# SCH_FINAL.net
KiCad netlist of a schematic drawn in EasyEDA
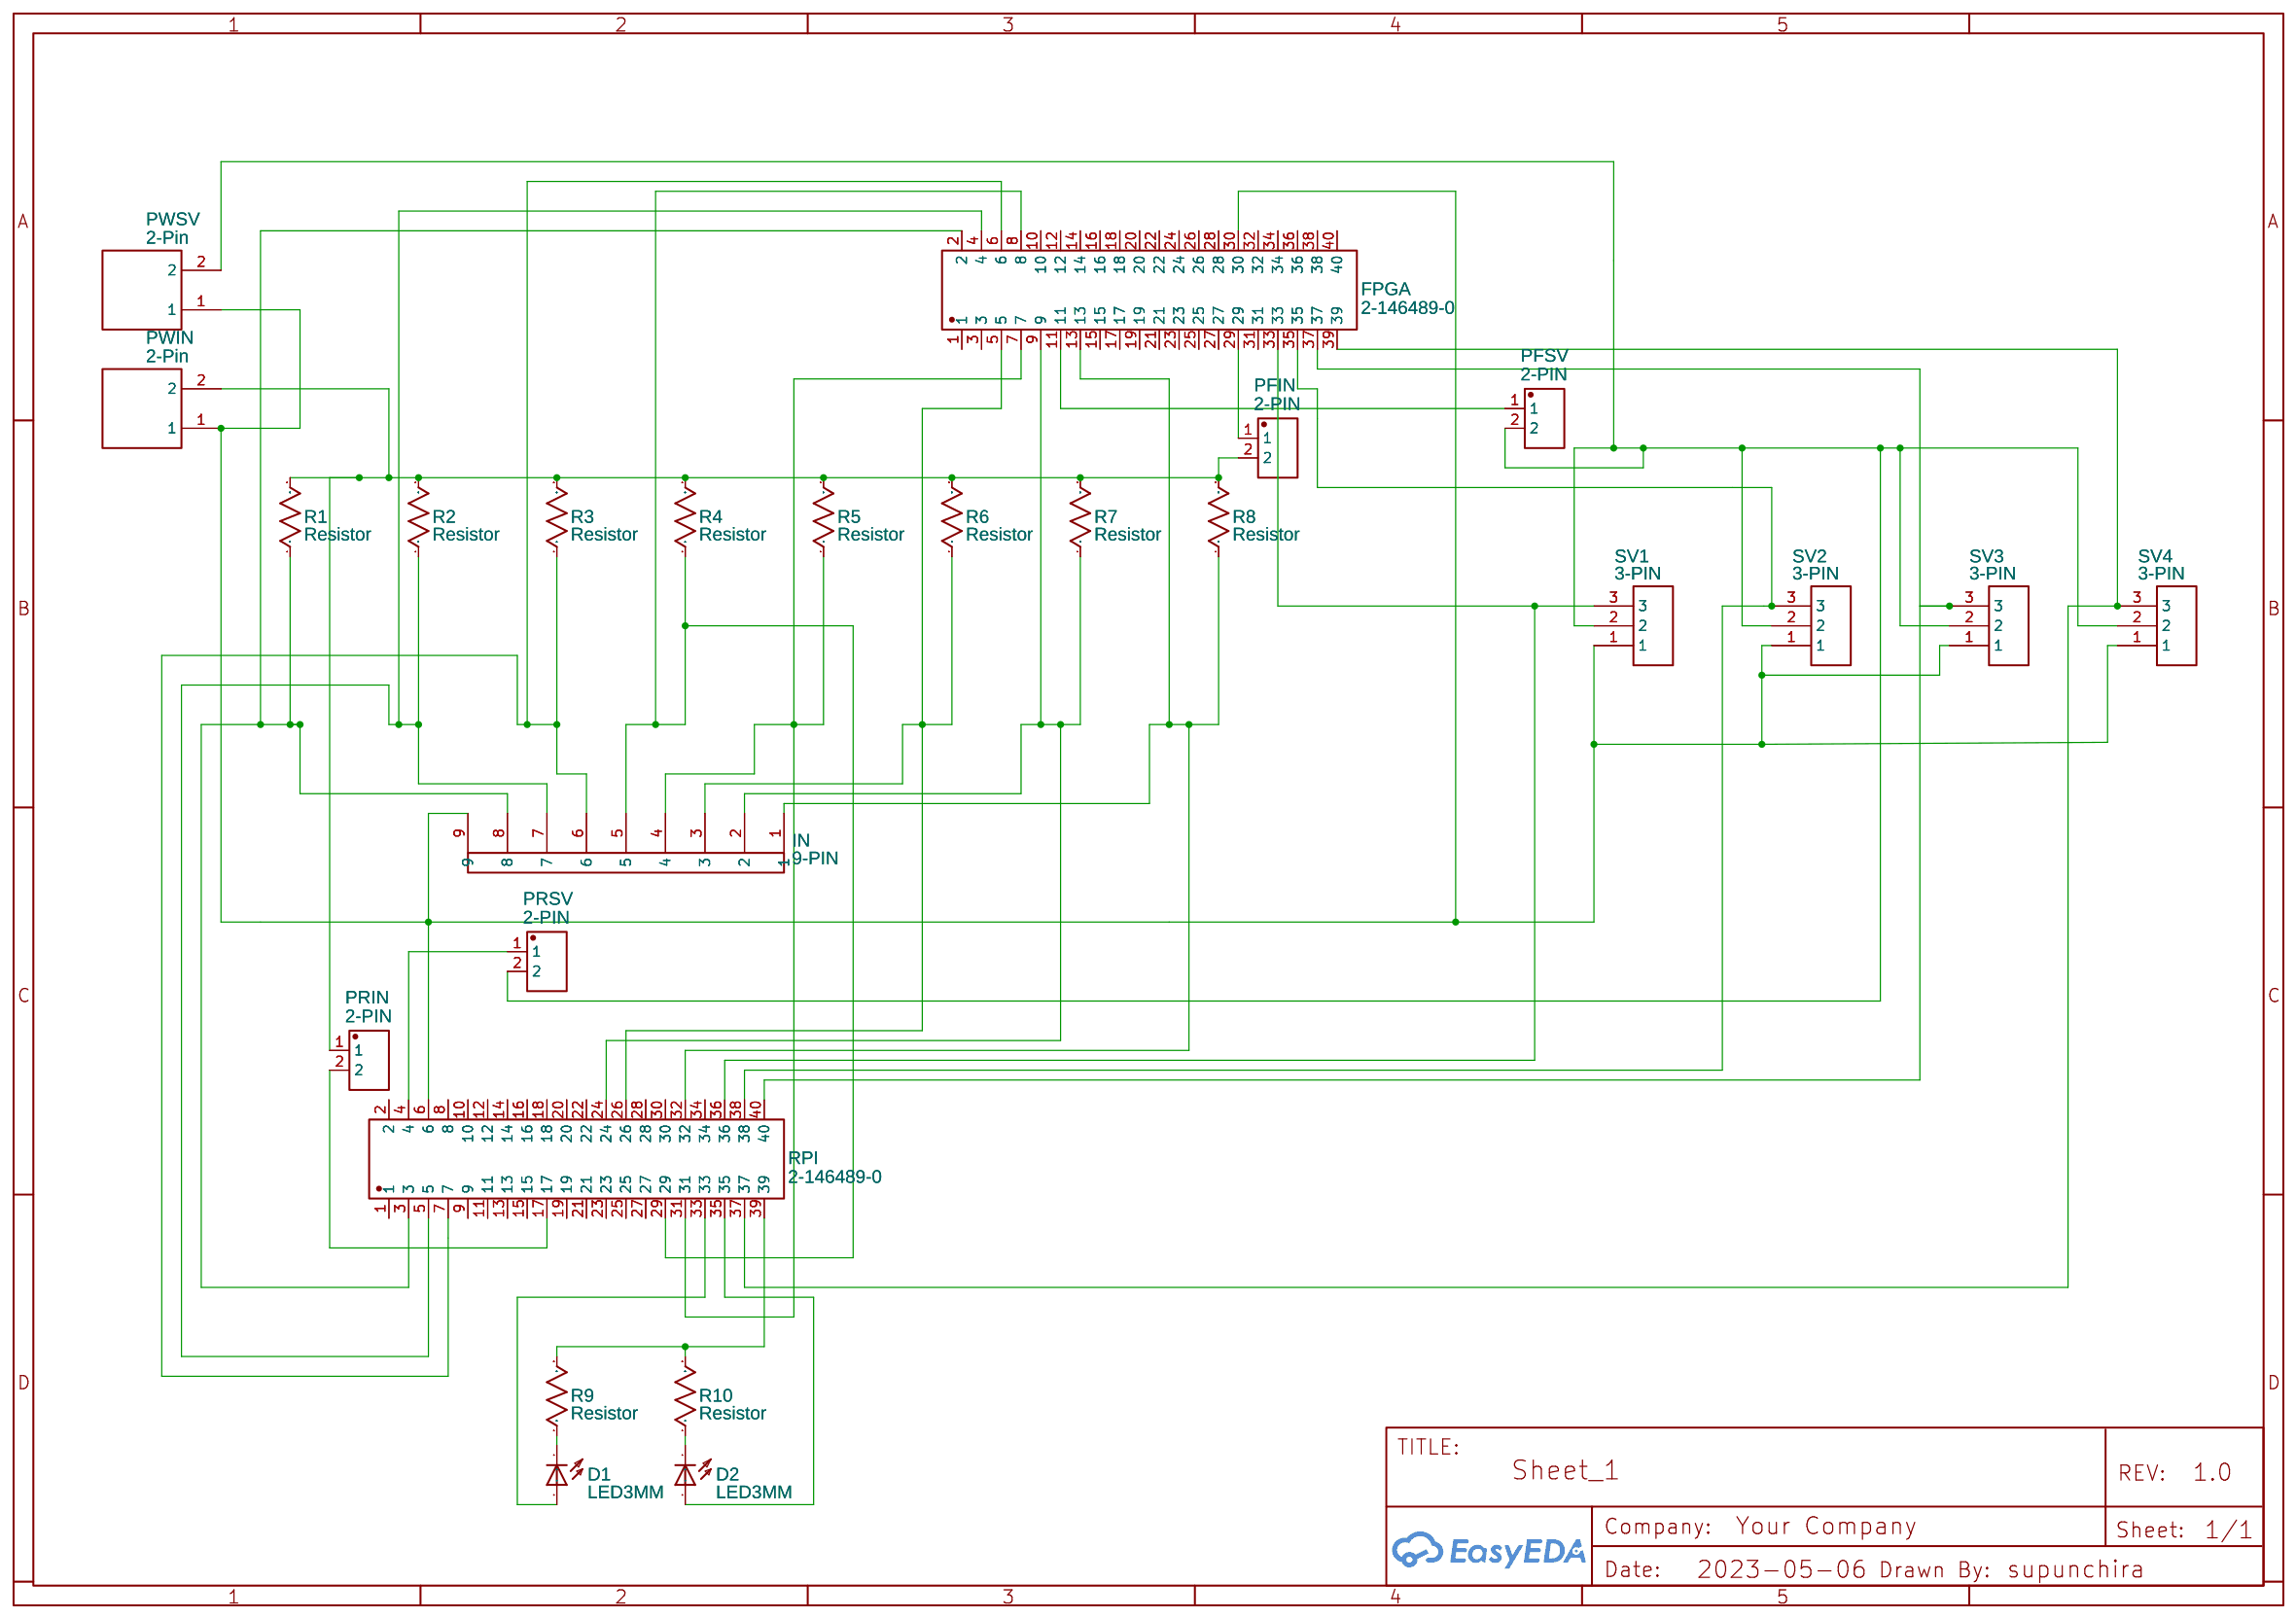
[diagram p0: schematic sheet]

(export (version "E")
  (design (tool "Eeschema 10.0.6"))
  (components
    (comp (ref "D1") (value "LED3MM") (libsource (lib "") (part "LED3MM")))
    (comp (ref "D2") (value "LED3MM") (libsource (lib "") (part "LED3MM")))
    (comp (ref "FPGA")
      (value "2-146489-0")
      (fields (field (name "BOM_Supplier Part") "C3334839"))
      (libsource (lib "") (part "2-146489-0_1"))
    )
    (comp (ref "IN") (value "9-PIN") (libsource (lib "") (part "Header9Pin")))
    (comp (ref "PFIN")
      (value "2-PIN")
      (fields
        (field (name "BOM_Manufacturer Part") "Terminals/WJ2EDGV-5.08-8P")
        (field (name "BOM_Supplier Part") "C23595")
      )
      (libsource (lib "") (part "2-PIN-MALE-CONNECTOR COPY_2"))
    )
    (comp (ref "PFSV")
      (value "2-PIN")
      (fields
        (field (name "BOM_Manufacturer Part") "Terminals/WJ2EDGV-5.08-8P")
        (field (name "BOM_Supplier Part") "C23595")
      )
      (libsource (lib "") (part "2-PIN-MALE-CONNECTOR COPY_1"))
    )
    (comp (ref "PRIN")
      (value "2-PIN")
      (fields
        (field (name "BOM_Manufacturer Part") "Terminals/WJ2EDGV-5.08-8P")
        (field (name "BOM_Supplier Part") "C23595")
      )
      (libsource (lib "") (part "2-PIN-MALE-CONNECTOR COPY"))
    )
    (comp (ref "PRSV")
      (value "2-PIN")
      (fields
        (field (name "BOM_Manufacturer Part") "Terminals/WJ2EDGV-5.08-8P")
        (field (name "BOM_Supplier Part") "C23595")
      )
      (libsource (lib "") (part "2-PIN-MALE-CONNECTOR COPY_3"))
    )
    (comp (ref "PWIN") (value "2-Pin") (libsource (lib "") (part "2-Pin-Male-Header-2.54mm_1")))
    (comp (ref "PWSV") (value "2-Pin") (libsource (lib "") (part "2-Pin-Male-Header-2.54mm")))
    (comp (ref "R1") (value "Resistor") (libsource (lib "") (part "Resistor")))
    (comp (ref "R2") (value "Resistor") (libsource (lib "") (part "Resistor")))
    (comp (ref "R3") (value "Resistor") (libsource (lib "") (part "Resistor")))
    (comp (ref "R4") (value "Resistor") (libsource (lib "") (part "Resistor")))
    (comp (ref "R5") (value "Resistor") (libsource (lib "") (part "Resistor")))
    (comp (ref "R6") (value "Resistor") (libsource (lib "") (part "Resistor")))
    (comp (ref "R7") (value "Resistor") (libsource (lib "") (part "Resistor")))
    (comp (ref "R8") (value "Resistor") (libsource (lib "") (part "Resistor")))
    (comp (ref "R9") (value "Resistor") (libsource (lib "") (part "Resistor")))
    (comp (ref "R10") (value "Resistor") (libsource (lib "") (part "Resistor")))
    (comp (ref "RPI")
      (value "2-146489-0")
      (fields (field (name "BOM_Supplier Part") "C3334839"))
      (libsource (lib "") (part "2-146489-0"))
    )
    (comp (ref "SV1") (value "3-PIN") (libsource (lib "") (part "3-PIN")))
    (comp (ref "SV2") (value "3-PIN") (libsource (lib "") (part "3-PIN")))
    (comp (ref "SV3") (value "3-PIN") (libsource (lib "") (part "3-PIN")))
    (comp (ref "SV4") (value "3-PIN") (libsource (lib "") (part "3-PIN")))
  )
  (nets
    (net (code "1") (name "Net-(D1-C)") (class "Default")
      (node (ref "D1") (pin "K") (pinfunction "C_K") (pintype "bidirectional"))
      (node (ref "R9") (pin "1") (pinfunction "P1_1") (pintype "unspecified"))
    )
    (net (code "2") (name "Net-(D1-PadA)") (class "Default")
      (node (ref "D1") (pin "A") (pinfunction "A_A") (pintype "bidirectional"))
      (node (ref "RPI") (pin "33") (pinfunction "33_33") (pintype "unspecified"))
    )
    (net (code "3") (name "Net-(D2-C)") (class "Default")
      (node (ref "D2") (pin "K") (pinfunction "C_K") (pintype "bidirectional"))
      (node (ref "R10") (pin "1") (pinfunction "P1_1") (pintype "unspecified"))
    )
    (net (code "4") (name "Net-(D2-PadA)") (class "Default")
      (node (ref "D2") (pin "A") (pinfunction "A_A") (pintype "bidirectional"))
      (node (ref "RPI") (pin "35") (pinfunction "35_35") (pintype "unspecified"))
    )
    (net (code "5") (name "Net-(FPGA-Pad11)") (class "Default")
      (node (ref "FPGA") (pin "11") (pinfunction "11_11") (pintype "unspecified"))
      (node (ref "PFSV") (pin "1") (pinfunction "1_1") (pintype "unspecified"))
    )
    (net (code "6") (name "Net-(FPGA-Pad29)") (class "Default")
      (node (ref "FPGA") (pin "29") (pinfunction "29_29") (pintype "unspecified"))
      (node (ref "PFIN") (pin "1") (pinfunction "1_1") (pintype "unspecified"))
    )
    (net (code "7") (name "Net-(FPGA-Pad30)") (class "Default")
      (node (ref "FPGA") (pin "30") (pinfunction "30_30") (pintype "unspecified"))
      (node (ref "IN") (pin "9") (pinfunction "9_9") (pintype "unspecified"))
      (node (ref "PWIN") (pin "1") (pinfunction "1_1") (pintype "unspecified"))
      (node (ref "PWSV") (pin "1") (pinfunction "1_1") (pintype "unspecified"))
      (node (ref "RPI") (pin "6") (pinfunction "6_6") (pintype "unspecified"))
      (node (ref "SV1") (pin "1") (pinfunction "1_1") (pintype "unspecified"))
      (node (ref "SV2") (pin "1") (pinfunction "1_1") (pintype "unspecified"))
      (node (ref "SV3") (pin "1") (pinfunction "1_1") (pintype "unspecified"))
      (node (ref "SV4") (pin "1") (pinfunction "1_1") (pintype "unspecified"))
    )
    (net (code "8") (name "Net-(FPGA-Pad33)") (class "Default")
      (node (ref "FPGA") (pin "33") (pinfunction "33_33") (pintype "unspecified"))
      (node (ref "RPI") (pin "36") (pinfunction "36_36") (pintype "unspecified"))
      (node (ref "SV1") (pin "3") (pinfunction "3_3") (pintype "unspecified"))
    )
    (net (code "9") (name "Net-(FPGA-Pad35)") (class "Default")
      (node (ref "FPGA") (pin "35") (pinfunction "35_35") (pintype "unspecified"))
      (node (ref "RPI") (pin "38") (pinfunction "38_38") (pintype "unspecified"))
      (node (ref "SV2") (pin "3") (pinfunction "3_3") (pintype "unspecified"))
    )
    (net (code "10") (name "Net-(FPGA-Pad37)") (class "Default")
      (node (ref "FPGA") (pin "37") (pinfunction "37_37") (pintype "unspecified"))
      (node (ref "RPI") (pin "40") (pinfunction "40_40") (pintype "unspecified"))
      (node (ref "SV3") (pin "3") (pinfunction "3_3") (pintype "unspecified"))
    )
    (net (code "11") (name "Net-(FPGA-Pad39)") (class "Default")
      (node (ref "FPGA") (pin "39") (pinfunction "39_39") (pintype "unspecified"))
      (node (ref "RPI") (pin "37") (pinfunction "37_37") (pintype "unspecified"))
      (node (ref "SV4") (pin "3") (pinfunction "3_3") (pintype "unspecified"))
    )
    (net (code "12") (name "Net-(PFSV-Pad2)") (class "Default")
      (node (ref "PFSV") (pin "2") (pinfunction "2_2") (pintype "unspecified"))
      (node (ref "PRSV") (pin "2") (pinfunction "2_2") (pintype "unspecified"))
      (node (ref "PWSV") (pin "2") (pinfunction "2_2") (pintype "unspecified"))
      (node (ref "SV1") (pin "2") (pinfunction "2_2") (pintype "unspecified"))
      (node (ref "SV2") (pin "2") (pinfunction "2_2") (pintype "unspecified"))
      (node (ref "SV3") (pin "2") (pinfunction "2_2") (pintype "unspecified"))
      (node (ref "SV4") (pin "2") (pinfunction "2_2") (pintype "unspecified"))
    )
    (net (code "13") (name "Net-(PRIN-Pad2)") (class "Default")
      (node (ref "PRIN") (pin "2") (pinfunction "2_2") (pintype "unspecified"))
      (node (ref "RPI") (pin "17") (pinfunction "17_17") (pintype "unspecified"))
    )
    (net (code "14") (name "Net-(PRSV-Pad1)") (class "Default")
      (node (ref "PRSV") (pin "1") (pinfunction "1_1") (pintype "unspecified"))
      (node (ref "RPI") (pin "4") (pinfunction "4_4") (pintype "unspecified"))
    )
    (net (code "15") (name "Net-(R1-P1)") (class "Default")
      (node (ref "FPGA") (pin "2") (pinfunction "2_2") (pintype "unspecified"))
      (node (ref "IN") (pin "8") (pinfunction "8_8") (pintype "unspecified"))
      (node (ref "R1") (pin "1") (pinfunction "P1_1") (pintype "unspecified"))
      (node (ref "RPI") (pin "3") (pinfunction "3_3") (pintype "unspecified"))
    )
    (net (code "16") (name "Net-(R1-P2)") (class "Default")
      (node (ref "PFIN") (pin "2") (pinfunction "2_2") (pintype "unspecified"))
      (node (ref "PRIN") (pin "1") (pinfunction "1_1") (pintype "unspecified"))
      (node (ref "PWIN") (pin "2") (pinfunction "2_2") (pintype "unspecified"))
      (node (ref "R1") (pin "2") (pinfunction "P2_2") (pintype "unspecified"))
      (node (ref "R2") (pin "2") (pinfunction "P2_2") (pintype "unspecified"))
      (node (ref "R3") (pin "2") (pinfunction "P2_2") (pintype "unspecified"))
      (node (ref "R4") (pin "2") (pinfunction "P2_2") (pintype "unspecified"))
      (node (ref "R5") (pin "2") (pinfunction "P2_2") (pintype "unspecified"))
      (node (ref "R6") (pin "2") (pinfunction "P2_2") (pintype "unspecified"))
      (node (ref "R7") (pin "2") (pinfunction "P2_2") (pintype "unspecified"))
      (node (ref "R8") (pin "2") (pinfunction "P2_2") (pintype "unspecified"))
    )
    (net (code "17") (name "Net-(R2-P1)") (class "Default")
      (node (ref "FPGA") (pin "4") (pinfunction "4_4") (pintype "unspecified"))
      (node (ref "IN") (pin "7") (pinfunction "7_7") (pintype "unspecified"))
      (node (ref "R2") (pin "1") (pinfunction "P1_1") (pintype "unspecified"))
      (node (ref "RPI") (pin "5") (pinfunction "5_5") (pintype "unspecified"))
    )
    (net (code "18") (name "Net-(R3-P1)") (class "Default")
      (node (ref "FPGA") (pin "6") (pinfunction "6_6") (pintype "unspecified"))
      (node (ref "IN") (pin "6") (pinfunction "6_6") (pintype "unspecified"))
      (node (ref "R3") (pin "1") (pinfunction "P1_1") (pintype "unspecified"))
      (node (ref "RPI") (pin "7") (pinfunction "7_7") (pintype "unspecified"))
    )
    (net (code "19") (name "Net-(R4-P1)") (class "Default")
      (node (ref "FPGA") (pin "8") (pinfunction "8_8") (pintype "unspecified"))
      (node (ref "IN") (pin "5") (pinfunction "5_5") (pintype "unspecified"))
      (node (ref "R4") (pin "1") (pinfunction "P1_1") (pintype "unspecified"))
      (node (ref "RPI") (pin "29") (pinfunction "29_29") (pintype "unspecified"))
    )
    (net (code "20") (name "Net-(R5-P1)") (class "Default")
      (node (ref "FPGA") (pin "7") (pinfunction "7_7") (pintype "unspecified"))
      (node (ref "IN") (pin "4") (pinfunction "4_4") (pintype "unspecified"))
      (node (ref "R5") (pin "1") (pinfunction "P1_1") (pintype "unspecified"))
      (node (ref "RPI") (pin "31") (pinfunction "31_31") (pintype "unspecified"))
    )
    (net (code "21") (name "Net-(R6-P1)") (class "Default")
      (node (ref "FPGA") (pin "5") (pinfunction "5_5") (pintype "unspecified"))
      (node (ref "IN") (pin "3") (pinfunction "3_3") (pintype "unspecified"))
      (node (ref "R6") (pin "1") (pinfunction "P1_1") (pintype "unspecified"))
      (node (ref "RPI") (pin "26") (pinfunction "26_26") (pintype "unspecified"))
    )
    (net (code "22") (name "Net-(R7-P1)") (class "Default")
      (node (ref "FPGA") (pin "9") (pinfunction "9_9") (pintype "unspecified"))
      (node (ref "IN") (pin "2") (pinfunction "2_2") (pintype "unspecified"))
      (node (ref "R7") (pin "1") (pinfunction "P1_1") (pintype "unspecified"))
      (node (ref "RPI") (pin "24") (pinfunction "24_24") (pintype "unspecified"))
    )
    (net (code "23") (name "Net-(R8-P1)") (class "Default")
      (node (ref "FPGA") (pin "13") (pinfunction "13_13") (pintype "unspecified"))
      (node (ref "IN") (pin "1") (pinfunction "1_1") (pintype "unspecified"))
      (node (ref "R8") (pin "1") (pinfunction "P1_1") (pintype "unspecified"))
      (node (ref "RPI") (pin "32") (pinfunction "32_32") (pintype "unspecified"))
    )
    (net (code "24") (name "Net-(R10-P2)") (class "Default")
      (node (ref "R10") (pin "2") (pinfunction "P2_2") (pintype "unspecified"))
      (node (ref "R9") (pin "2") (pinfunction "P2_2") (pintype "unspecified"))
      (node (ref "RPI") (pin "39") (pinfunction "39_39") (pintype "unspecified"))
    )
    (net (code "25") (name "unconnected-(FPGA-Pad1)") (class "Default")
      (node (ref "FPGA") (pin "1") (pinfunction "1_1") (pintype "unspecified"))
    )
    (net (code "26") (name "unconnected-(FPGA-Pad3)") (class "Default")
      (node (ref "FPGA") (pin "3") (pinfunction "3_3") (pintype "unspecified"))
    )
    (net (code "27") (name "unconnected-(FPGA-Pad10)") (class "Default")
      (node (ref "FPGA") (pin "10") (pinfunction "10_10") (pintype "unspecified"))
    )
    (net (code "28") (name "unconnected-(FPGA-Pad12)") (class "Default")
      (node (ref "FPGA") (pin "12") (pinfunction "12_12") (pintype "unspecified"))
    )
    (net (code "29") (name "unconnected-(FPGA-Pad14)") (class "Default")
      (node (ref "FPGA") (pin "14") (pinfunction "14_14") (pintype "unspecified"))
    )
    (net (code "30") (name "unconnected-(FPGA-Pad15)") (class "Default")
      (node (ref "FPGA") (pin "15") (pinfunction "15_15") (pintype "unspecified"))
    )
    (net (code "31") (name "unconnected-(FPGA-Pad16)") (class "Default")
      (node (ref "FPGA") (pin "16") (pinfunction "16_16") (pintype "unspecified"))
    )
    (net (code "32") (name "unconnected-(FPGA-Pad17)") (class "Default")
      (node (ref "FPGA") (pin "17") (pinfunction "17_17") (pintype "unspecified"))
    )
    (net (code "33") (name "unconnected-(FPGA-Pad18)") (class "Default")
      (node (ref "FPGA") (pin "18") (pinfunction "18_18") (pintype "unspecified"))
    )
    (net (code "34") (name "unconnected-(FPGA-Pad19)") (class "Default")
      (node (ref "FPGA") (pin "19") (pinfunction "19_19") (pintype "unspecified"))
    )
    (net (code "35") (name "unconnected-(FPGA-Pad20)") (class "Default")
      (node (ref "FPGA") (pin "20") (pinfunction "20_20") (pintype "unspecified"))
    )
    (net (code "36") (name "unconnected-(FPGA-Pad21)") (class "Default")
      (node (ref "FPGA") (pin "21") (pinfunction "21_21") (pintype "unspecified"))
    )
    (net (code "37") (name "unconnected-(FPGA-Pad22)") (class "Default")
      (node (ref "FPGA") (pin "22") (pinfunction "22_22") (pintype "unspecified"))
    )
    (net (code "38") (name "unconnected-(FPGA-Pad23)") (class "Default")
      (node (ref "FPGA") (pin "23") (pinfunction "23_23") (pintype "unspecified"))
    )
    (net (code "39") (name "unconnected-(FPGA-Pad24)") (class "Default")
      (node (ref "FPGA") (pin "24") (pinfunction "24_24") (pintype "unspecified"))
    )
    (net (code "40") (name "unconnected-(FPGA-Pad25)") (class "Default")
      (node (ref "FPGA") (pin "25") (pinfunction "25_25") (pintype "unspecified"))
    )
    (net (code "41") (name "unconnected-(FPGA-Pad26)") (class "Default")
      (node (ref "FPGA") (pin "26") (pinfunction "26_26") (pintype "unspecified"))
    )
    (net (code "42") (name "unconnected-(FPGA-Pad27)") (class "Default")
      (node (ref "FPGA") (pin "27") (pinfunction "27_27") (pintype "unspecified"))
    )
    (net (code "43") (name "unconnected-(FPGA-Pad28)") (class "Default")
      (node (ref "FPGA") (pin "28") (pinfunction "28_28") (pintype "unspecified"))
    )
    (net (code "44") (name "unconnected-(FPGA-Pad31)") (class "Default")
      (node (ref "FPGA") (pin "31") (pinfunction "31_31") (pintype "unspecified"))
    )
    (net (code "45") (name "unconnected-(FPGA-Pad32)") (class "Default")
      (node (ref "FPGA") (pin "32") (pinfunction "32_32") (pintype "unspecified"))
    )
    (net (code "46") (name "unconnected-(FPGA-Pad34)") (class "Default")
      (node (ref "FPGA") (pin "34") (pinfunction "34_34") (pintype "unspecified"))
    )
    (net (code "47") (name "unconnected-(FPGA-Pad36)") (class "Default")
      (node (ref "FPGA") (pin "36") (pinfunction "36_36") (pintype "unspecified"))
    )
    (net (code "48") (name "unconnected-(FPGA-Pad38)") (class "Default")
      (node (ref "FPGA") (pin "38") (pinfunction "38_38") (pintype "unspecified"))
    )
    (net (code "49") (name "unconnected-(FPGA-Pad40)") (class "Default")
      (node (ref "FPGA") (pin "40") (pinfunction "40_40") (pintype "unspecified"))
    )
    (net (code "50") (name "unconnected-(RPI-Pad1)") (class "Default")
      (node (ref "RPI") (pin "1") (pinfunction "1_1") (pintype "unspecified"))
    )
    (net (code "51") (name "unconnected-(RPI-Pad2)") (class "Default")
      (node (ref "RPI") (pin "2") (pinfunction "2_2") (pintype "unspecified"))
    )
    (net (code "52") (name "unconnected-(RPI-Pad8)") (class "Default")
      (node (ref "RPI") (pin "8") (pinfunction "8_8") (pintype "unspecified"))
    )
    (net (code "53") (name "unconnected-(RPI-Pad9)") (class "Default")
      (node (ref "RPI") (pin "9") (pinfunction "9_9") (pintype "unspecified"))
    )
    (net (code "54") (name "unconnected-(RPI-Pad10)") (class "Default")
      (node (ref "RPI") (pin "10") (pinfunction "10_10") (pintype "unspecified"))
    )
    (net (code "55") (name "unconnected-(RPI-Pad11)") (class "Default")
      (node (ref "RPI") (pin "11") (pinfunction "11_11") (pintype "unspecified"))
    )
    (net (code "56") (name "unconnected-(RPI-Pad12)") (class "Default")
      (node (ref "RPI") (pin "12") (pinfunction "12_12") (pintype "unspecified"))
    )
    (net (code "57") (name "unconnected-(RPI-Pad13)") (class "Default")
      (node (ref "RPI") (pin "13") (pinfunction "13_13") (pintype "unspecified"))
    )
    (net (code "58") (name "unconnected-(RPI-Pad14)") (class "Default")
      (node (ref "RPI") (pin "14") (pinfunction "14_14") (pintype "unspecified"))
    )
    (net (code "59") (name "unconnected-(RPI-Pad15)") (class "Default")
      (node (ref "RPI") (pin "15") (pinfunction "15_15") (pintype "unspecified"))
    )
    (net (code "60") (name "unconnected-(RPI-Pad16)") (class "Default")
      (node (ref "RPI") (pin "16") (pinfunction "16_16") (pintype "unspecified"))
    )
    (net (code "61") (name "unconnected-(RPI-Pad18)") (class "Default")
      (node (ref "RPI") (pin "18") (pinfunction "18_18") (pintype "unspecified"))
    )
    (net (code "62") (name "unconnected-(RPI-Pad19)") (class "Default")
      (node (ref "RPI") (pin "19") (pinfunction "19_19") (pintype "unspecified"))
    )
    (net (code "63") (name "unconnected-(RPI-Pad20)") (class "Default")
      (node (ref "RPI") (pin "20") (pinfunction "20_20") (pintype "unspecified"))
    )
    (net (code "64") (name "unconnected-(RPI-Pad21)") (class "Default")
      (node (ref "RPI") (pin "21") (pinfunction "21_21") (pintype "unspecified"))
    )
    (net (code "65") (name "unconnected-(RPI-Pad22)") (class "Default")
      (node (ref "RPI") (pin "22") (pinfunction "22_22") (pintype "unspecified"))
    )
    (net (code "66") (name "unconnected-(RPI-Pad23)") (class "Default")
      (node (ref "RPI") (pin "23") (pinfunction "23_23") (pintype "unspecified"))
    )
    (net (code "67") (name "unconnected-(RPI-Pad25)") (class "Default")
      (node (ref "RPI") (pin "25") (pinfunction "25_25") (pintype "unspecified"))
    )
    (net (code "68") (name "unconnected-(RPI-Pad27)") (class "Default")
      (node (ref "RPI") (pin "27") (pinfunction "27_27") (pintype "unspecified"))
    )
    (net (code "69") (name "unconnected-(RPI-Pad28)") (class "Default")
      (node (ref "RPI") (pin "28") (pinfunction "28_28") (pintype "unspecified"))
    )
    (net (code "70") (name "unconnected-(RPI-Pad30)") (class "Default")
      (node (ref "RPI") (pin "30") (pinfunction "30_30") (pintype "unspecified"))
    )
    (net (code "71") (name "unconnected-(RPI-Pad34)") (class "Default")
      (node (ref "RPI") (pin "34") (pinfunction "34_34") (pintype "unspecified"))
    )
  )
)
